# 4x4v3.net
KiCad netlist of a schematic drawn in EAGLE
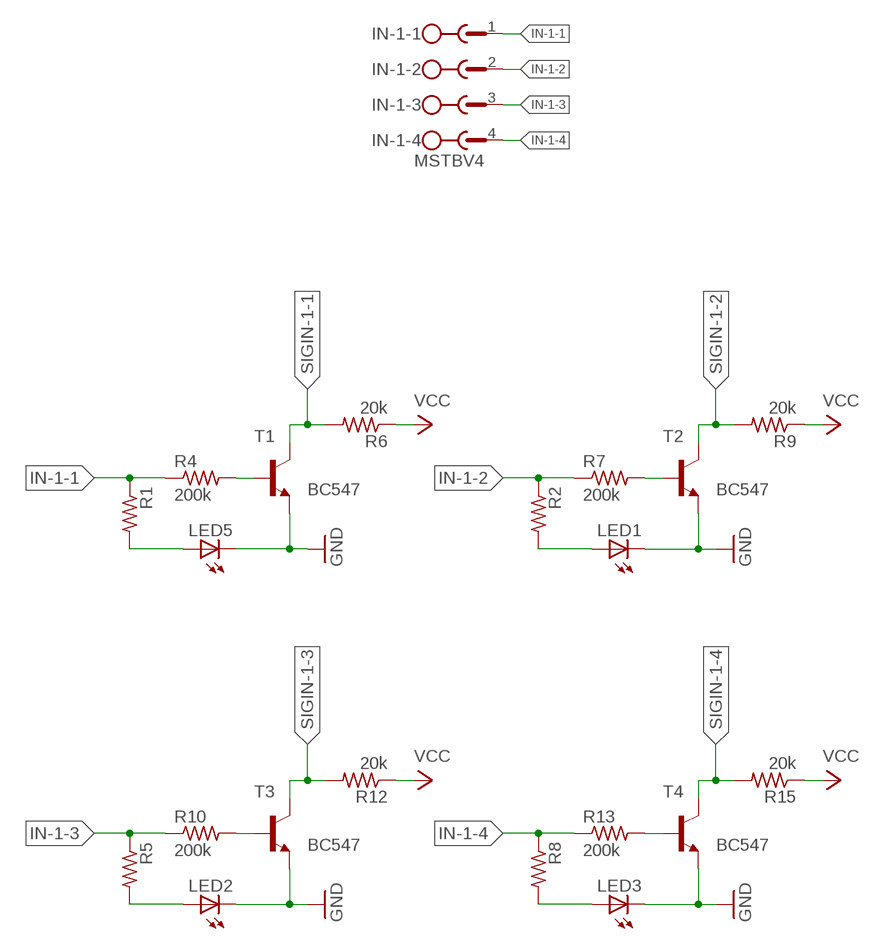
[diagram p0: schematic, sheet 1, part 1 of 2]
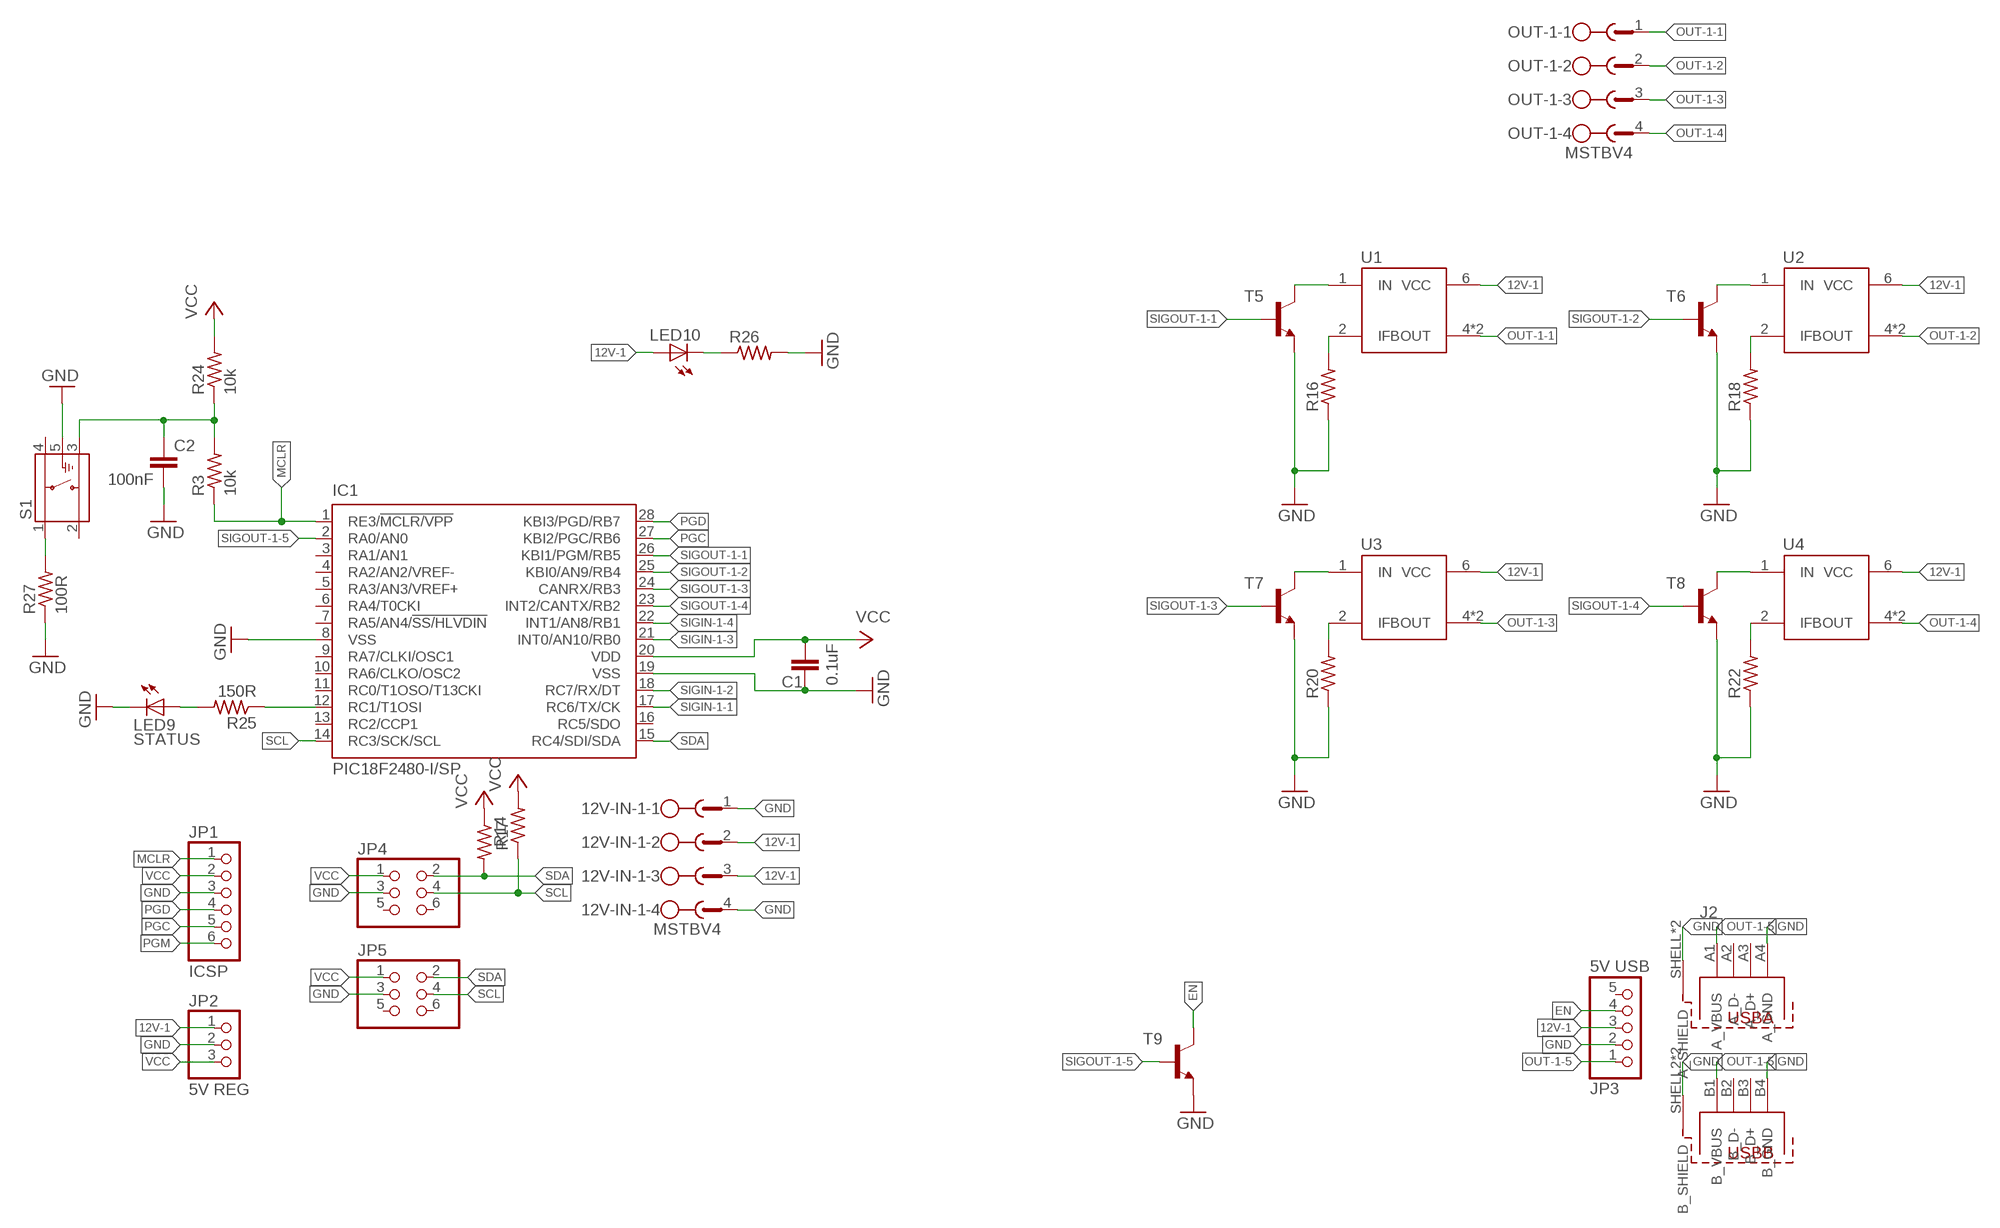
[diagram p1: schematic, sheet 1, part 2 of 2]

(export (version "E")
  (design (tool "Eeschema 10.0.6"))
  (components
    (comp (ref "12V-IN-1")
      (value "MSTBV4")
      (footprint "eagle-import:MSTBV4")
      (fields (field (name "MPN") "MSTBV 2,5/4-GF-5.08"))
      (libsource (lib "eagle-import") (part "MSTBV4"))
    )
    (comp (ref "C1")
      (value "0.1uF")
      (footprint "eagle-import:C025-030X050")
      (libsource (lib "eagle-import") (part "C-EU025-030X050"))
    )
    (comp (ref "C2")
      (value "100nF")
      (footprint "eagle-import:C025-025X050")
      (libsource (lib "eagle-import") (part "C-EU025-025X050"))
    )
    (comp (ref "IC1")
      (value "PIC18F2480-I/SP")
      (footprint "eagle-import:DIL28-3")
      (fields (field (name "MF") "MICROCHIP"))
      (libsource (lib "eagle-import") (part "PIC18F280-I/SP4"))
    )
    (comp (ref "IN-1")
      (value "MSTBV4")
      (footprint "eagle-import:MSTBV4")
      (fields (field (name "MPN") "MSTBV 2,5/4-GF-5.08"))
      (libsource (lib "eagle-import") (part "MSTBV4"))
    )
    (comp (ref "J2")
      (value "614008235023")
      (footprint "eagle-import:614008235023")
      (libsource (lib "eagle-import") (part "614008235023"))
    )
    (comp (ref "JP1")
      (value "ICSP")
      (footprint "eagle-import:1X06")
      (libsource (lib "eagle-import") (part "PINHD-1X6"))
    )
    (comp (ref "JP2")
      (value "5V REG")
      (footprint "eagle-import:1X03")
      (libsource (lib "eagle-import") (part "PINHD-1X3"))
    )
    (comp (ref "JP3")
      (value "5V USB")
      (footprint "eagle-import:1X05")
      (libsource (lib "eagle-import") (part "PINHD-1X5"))
    )
    (comp (ref "JP4")
      (value "PINHD-2X3")
      (footprint "eagle-import:2X03")
      (libsource (lib "eagle-import") (part "PINHD-2X3"))
    )
    (comp (ref "JP5")
      (value "PINHD-2X3")
      (footprint "eagle-import:2X03")
      (libsource (lib "eagle-import") (part "PINHD-2X3"))
    )
    (comp (ref "LED1")
      (value "LEDCHIPLED_0805")
      (footprint "eagle-import:CHIPLED_0805")
      (libsource (lib "eagle-import") (part "LEDCHIPLED_0805"))
    )
    (comp (ref "LED2")
      (value "LEDCHIPLED_0805")
      (footprint "eagle-import:CHIPLED_0805")
      (libsource (lib "eagle-import") (part "LEDCHIPLED_0805"))
    )
    (comp (ref "LED3")
      (value "LEDCHIPLED_0805")
      (footprint "eagle-import:CHIPLED_0805")
      (libsource (lib "eagle-import") (part "LEDCHIPLED_0805"))
    )
    (comp (ref "LED5")
      (value "LEDCHIPLED_0805")
      (footprint "eagle-import:CHIPLED_0805")
      (libsource (lib "eagle-import") (part "LEDCHIPLED_0805"))
    )
    (comp (ref "LED9")
      (value "STATUS")
      (footprint "eagle-import:CHIPLED_0805")
      (libsource (lib "eagle-import") (part "LEDCHIPLED_0805"))
    )
    (comp (ref "LED10")
      (value "LEDCHIPLED_0805")
      (footprint "eagle-import:CHIPLED_0805")
      (libsource (lib "eagle-import") (part "LEDCHIPLED_0805"))
    )
    (comp (ref "OUT-1")
      (value "MSTBV4")
      (footprint "eagle-import:MSTBV4")
      (fields (field (name "MPN") "MSTBV 2,5/4-GF-5.08"))
      (libsource (lib "eagle-import") (part "MSTBV4"))
    )
    (comp (ref "R1")
      (value "R-US_R0805")
      (footprint "eagle-import:R0805")
      (libsource (lib "eagle-import") (part "R-US_R0805"))
    )
    (comp (ref "R2")
      (value "R-US_R0805")
      (footprint "eagle-import:R0805")
      (libsource (lib "eagle-import") (part "R-US_R0805"))
    )
    (comp (ref "R3")
      (value "10k")
      (footprint "eagle-import:R0805")
      (libsource (lib "eagle-import") (part "R-US_R0805"))
    )
    (comp (ref "R4")
      (value "200k")
      (footprint "eagle-import:R0805")
      (libsource (lib "eagle-import") (part "R-US_R0805"))
    )
    (comp (ref "R5")
      (value "R-US_R0805")
      (footprint "eagle-import:R0805")
      (libsource (lib "eagle-import") (part "R-US_R0805"))
    )
    (comp (ref "R6")
      (value "20k")
      (footprint "eagle-import:R0805")
      (libsource (lib "eagle-import") (part "R-US_R0805"))
    )
    (comp (ref "R7")
      (value "200k")
      (footprint "eagle-import:R0805")
      (libsource (lib "eagle-import") (part "R-US_R0805"))
    )
    (comp (ref "R8")
      (value "R-US_R0805")
      (footprint "eagle-import:R0805")
      (libsource (lib "eagle-import") (part "R-US_R0805"))
    )
    (comp (ref "R9")
      (value "20k")
      (footprint "eagle-import:R0805")
      (libsource (lib "eagle-import") (part "R-US_R0805"))
    )
    (comp (ref "R10")
      (value "200k")
      (footprint "eagle-import:R0805")
      (libsource (lib "eagle-import") (part "R-US_R0805"))
    )
    (comp (ref "R12")
      (value "20k")
      (footprint "eagle-import:R0805")
      (libsource (lib "eagle-import") (part "R-US_R0805"))
    )
    (comp (ref "R13")
      (value "200k")
      (footprint "eagle-import:R0805")
      (libsource (lib "eagle-import") (part "R-US_R0805"))
    )
    (comp (ref "R14")
      (value "R-US_R0805")
      (footprint "eagle-import:R0805")
      (libsource (lib "eagle-import") (part "R-US_R0805"))
    )
    (comp (ref "R15")
      (value "20k")
      (footprint "eagle-import:R0805")
      (libsource (lib "eagle-import") (part "R-US_R0805"))
    )
    (comp (ref "R16")
      (value "R-US_R0805")
      (footprint "eagle-import:R0805")
      (libsource (lib "eagle-import") (part "R-US_R0805"))
    )
    (comp (ref "R17")
      (value "R-US_R0805")
      (footprint "eagle-import:R0805")
      (libsource (lib "eagle-import") (part "R-US_R0805"))
    )
    (comp (ref "R18")
      (value "R-US_R0805")
      (footprint "eagle-import:R0805")
      (libsource (lib "eagle-import") (part "R-US_R0805"))
    )
    (comp (ref "R20")
      (value "R-US_R0805")
      (footprint "eagle-import:R0805")
      (libsource (lib "eagle-import") (part "R-US_R0805"))
    )
    (comp (ref "R22")
      (value "R-US_R0805")
      (footprint "eagle-import:R0805")
      (libsource (lib "eagle-import") (part "R-US_R0805"))
    )
    (comp (ref "R24")
      (value "10k")
      (footprint "eagle-import:R0805")
      (libsource (lib "eagle-import") (part "R-US_R0805"))
    )
    (comp (ref "R25")
      (value "150R")
      (footprint "eagle-import:R0805")
      (libsource (lib "eagle-import") (part "R-US_R0805"))
    )
    (comp (ref "R26")
      (value "R-US_R0805")
      (footprint "eagle-import:R0805")
      (libsource (lib "eagle-import") (part "R-US_R0805"))
    )
    (comp (ref "R27")
      (value "100R")
      (footprint "eagle-import:R0805")
      (libsource (lib "eagle-import") (part "R-US_R0805"))
    )
    (comp (ref "S1")
      (value "KMR421GULCLFS")
      (footprint "eagle-import:SW_KMR421GULCLFS")
      (fields (field (name "MF") "C&K Components"))
      (libsource (lib "eagle-import") (part "KMR421GULCLFS"))
    )
    (comp (ref "T1")
      (value "BC547")
      (footprint "eagle-import:SOT23-EBC")
      (libsource (lib "eagle-import") (part "-NPN-SOT23-EBC"))
    )
    (comp (ref "T2")
      (value "BC547")
      (footprint "eagle-import:SOT23-EBC")
      (libsource (lib "eagle-import") (part "-NPN-SOT23-EBC"))
    )
    (comp (ref "T3")
      (value "BC547")
      (footprint "eagle-import:SOT23-EBC")
      (libsource (lib "eagle-import") (part "-NPN-SOT23-EBC"))
    )
    (comp (ref "T4")
      (value "BC547")
      (footprint "eagle-import:SOT23-EBC")
      (libsource (lib "eagle-import") (part "-NPN-SOT23-EBC"))
    )
    (comp (ref "T5")
      (value "-NPN-SOT23-EBC")
      (footprint "eagle-import:SOT23-EBC")
      (libsource (lib "eagle-import") (part "-NPN-SOT23-EBC"))
    )
    (comp (ref "T6")
      (value "-NPN-SOT23-EBC")
      (footprint "eagle-import:SOT23-EBC")
      (libsource (lib "eagle-import") (part "-NPN-SOT23-EBC"))
    )
    (comp (ref "T7")
      (value "-NPN-SOT23-EBC")
      (footprint "eagle-import:SOT23-EBC")
      (libsource (lib "eagle-import") (part "-NPN-SOT23-EBC"))
    )
    (comp (ref "T8")
      (value "-NPN-SOT23-EBC")
      (footprint "eagle-import:SOT23-EBC")
      (libsource (lib "eagle-import") (part "-NPN-SOT23-EBC"))
    )
    (comp (ref "T9")
      (value "-NPN-SOT23-EBC")
      (footprint "eagle-import:SOT23-EBC")
      (libsource (lib "eagle-import") (part "-NPN-SOT23-EBC"))
    )
    (comp (ref "U1")
      (value "IR3315")
      (footprint "eagle-import:TO263-5")
      (libsource (lib "eagle-import") (part "IR3315"))
    )
    (comp (ref "U2")
      (value "IR3315")
      (footprint "eagle-import:TO263-5")
      (libsource (lib "eagle-import") (part "IR3315"))
    )
    (comp (ref "U3")
      (value "IR3315")
      (footprint "eagle-import:TO263-5")
      (libsource (lib "eagle-import") (part "IR3315"))
    )
    (comp (ref "U4")
      (value "IR3315")
      (footprint "eagle-import:TO263-5")
      (libsource (lib "eagle-import") (part "IR3315"))
    )
  )
  (nets
    (net (code "1") (name "12V-1") (class "Default")
      (node (ref "12V-IN-1") (pin "2") (pinfunction "1_2") (pintype "passive"))
      (node (ref "12V-IN-1") (pin "3") (pinfunction "1_3") (pintype "passive"))
      (node (ref "JP2") (pin "1") (pinfunction "1_1") (pintype "passive"))
      (node (ref "JP3") (pin "3") (pinfunction "3_3") (pintype "passive"))
      (node (ref "LED10") (pin "A") (pinfunction "A_A") (pintype "passive"))
      (node (ref "U1") (pin "6") (pinfunction "VCC_6") (pintype "bidirectional"))
      (node (ref "U2") (pin "6") (pinfunction "VCC_6") (pintype "bidirectional"))
      (node (ref "U3") (pin "6") (pinfunction "VCC_6") (pintype "bidirectional"))
      (node (ref "U4") (pin "6") (pinfunction "VCC_6") (pintype "bidirectional"))
    )
    (net (code "2") (name "EN") (class "Default")
      (node (ref "JP3") (pin "4") (pinfunction "4_4") (pintype "passive"))
      (node (ref "T9") (pin "C") (pinfunction "C_C") (pintype "passive"))
    )
    (net (code "3") (name "GND") (class "Default")
      (node (ref "12V-IN-1") (pin "1") (pinfunction "1_1") (pintype "passive"))
      (node (ref "12V-IN-1") (pin "4") (pinfunction "1_4") (pintype "passive"))
      (node (ref "C1") (pin "2") (pinfunction "2_2") (pintype "passive"))
      (node (ref "C2") (pin "2") (pinfunction "2_2") (pintype "passive"))
      (node (ref "IC1") (pin "19") (pinfunction "VSS_19") (pintype "power_in"))
      (node (ref "IC1") (pin "8") (pinfunction "VSS_8") (pintype "power_in"))
      (node (ref "J2") (pin "A4") (pinfunction "A_GND_A4") (pintype "bidirectional"))
      (node (ref "J2") (pin "B4") (pinfunction "B_GND_B4") (pintype "bidirectional"))
      (node (ref "J2") (pin "SHELL") (pinfunction "A_SHIELD_SHELL") (pintype "bidirectional"))
      (node (ref "J2") (pin "SHELL1") (pinfunction "A_SHIELD_SHELL1") (pintype "bidirectional"))
      (node (ref "J2") (pin "SHELL2") (pinfunction "B_SHIELD_SHELL2") (pintype "bidirectional"))
      (node (ref "J2") (pin "SHELL3") (pinfunction "B_SHIELD_SHELL3") (pintype "bidirectional"))
      (node (ref "JP1") (pin "3") (pinfunction "3_3") (pintype "passive"))
      (node (ref "JP2") (pin "2") (pinfunction "2_2") (pintype "passive"))
      (node (ref "JP3") (pin "2") (pinfunction "2_2") (pintype "passive"))
      (node (ref "JP4") (pin "3") (pinfunction "3_3") (pintype "passive"))
      (node (ref "JP5") (pin "3") (pinfunction "3_3") (pintype "passive"))
      (node (ref "LED1") (pin "C") (pinfunction "C_C") (pintype "passive"))
      (node (ref "LED2") (pin "C") (pinfunction "C_C") (pintype "passive"))
      (node (ref "LED3") (pin "C") (pinfunction "C_C") (pintype "passive"))
      (node (ref "LED5") (pin "C") (pinfunction "C_C") (pintype "passive"))
      (node (ref "LED9") (pin "C") (pinfunction "C_C") (pintype "passive"))
      (node (ref "R16") (pin "1") (pinfunction "1_1") (pintype "passive"))
      (node (ref "R18") (pin "1") (pinfunction "1_1") (pintype "passive"))
      (node (ref "R20") (pin "1") (pinfunction "1_1") (pintype "passive"))
      (node (ref "R22") (pin "1") (pinfunction "1_1") (pintype "passive"))
      (node (ref "R26") (pin "2") (pinfunction "2_2") (pintype "passive"))
      (node (ref "R27") (pin "1") (pinfunction "1_1") (pintype "passive"))
      (node (ref "S1") (pin "5") (pinfunction "G_5") (pintype "power_in"))
      (node (ref "T1") (pin "E") (pinfunction "E_E") (pintype "passive"))
      (node (ref "T2") (pin "E") (pinfunction "E_E") (pintype "passive"))
      (node (ref "T3") (pin "E") (pinfunction "E_E") (pintype "passive"))
      (node (ref "T4") (pin "E") (pinfunction "E_E") (pintype "passive"))
      (node (ref "T5") (pin "E") (pinfunction "E_E") (pintype "passive"))
      (node (ref "T6") (pin "E") (pinfunction "E_E") (pintype "passive"))
      (node (ref "T7") (pin "E") (pinfunction "E_E") (pintype "passive"))
      (node (ref "T8") (pin "E") (pinfunction "E_E") (pintype "passive"))
      (node (ref "T9") (pin "E") (pinfunction "E_E") (pintype "passive"))
    )
    (net (code "4") (name "IN-1-1") (class "Default")
      (node (ref "IN-1") (pin "1") (pinfunction "1_1") (pintype "passive"))
      (node (ref "R1") (pin "1") (pinfunction "1_1") (pintype "passive"))
      (node (ref "R4") (pin "1") (pinfunction "1_1") (pintype "passive"))
    )
    (net (code "5") (name "IN-1-2") (class "Default")
      (node (ref "IN-1") (pin "2") (pinfunction "1_2") (pintype "passive"))
      (node (ref "R2") (pin "1") (pinfunction "1_1") (pintype "passive"))
      (node (ref "R7") (pin "1") (pinfunction "1_1") (pintype "passive"))
    )
    (net (code "6") (name "IN-1-3") (class "Default")
      (node (ref "IN-1") (pin "3") (pinfunction "1_3") (pintype "passive"))
      (node (ref "R10") (pin "1") (pinfunction "1_1") (pintype "passive"))
      (node (ref "R5") (pin "1") (pinfunction "1_1") (pintype "passive"))
    )
    (net (code "7") (name "IN-1-4") (class "Default")
      (node (ref "IN-1") (pin "4") (pinfunction "1_4") (pintype "passive"))
      (node (ref "R13") (pin "1") (pinfunction "1_1") (pintype "passive"))
      (node (ref "R8") (pin "1") (pinfunction "1_1") (pintype "passive"))
    )
    (net (code "8") (name "MCLR") (class "Default")
      (node (ref "IC1") (pin "1") (pinfunction "RE3/~{MCLR/VPP}_1") (pintype "input"))
      (node (ref "JP1") (pin "1") (pinfunction "1_1") (pintype "passive"))
      (node (ref "R3") (pin "1") (pinfunction "1_1") (pintype "passive"))
    )
    (net (code "9") (name "Net-(C2-Pad1)") (class "Default")
      (node (ref "C2") (pin "1") (pinfunction "1_1") (pintype "passive"))
      (node (ref "R24") (pin "1") (pinfunction "1_1") (pintype "passive"))
      (node (ref "R3") (pin "2") (pinfunction "2_2") (pintype "passive"))
      (node (ref "S1") (pin "3") (pinfunction "3_3") (pintype "passive"))
    )
    (net (code "10") (name "Net-(IC1-RC1{slash}T1OSI)") (class "Default")
      (node (ref "IC1") (pin "12") (pinfunction "RC1/T1OSI_12") (pintype "bidirectional"))
      (node (ref "R25") (pin "1") (pinfunction "1_1") (pintype "passive"))
    )
    (net (code "11") (name "Net-(LED1-PadA)") (class "Default")
      (node (ref "LED1") (pin "A") (pinfunction "A_A") (pintype "passive"))
      (node (ref "R2") (pin "2") (pinfunction "2_2") (pintype "passive"))
    )
    (net (code "12") (name "Net-(LED2-PadA)") (class "Default")
      (node (ref "LED2") (pin "A") (pinfunction "A_A") (pintype "passive"))
      (node (ref "R5") (pin "2") (pinfunction "2_2") (pintype "passive"))
    )
    (net (code "13") (name "Net-(LED3-PadA)") (class "Default")
      (node (ref "LED3") (pin "A") (pinfunction "A_A") (pintype "passive"))
      (node (ref "R8") (pin "2") (pinfunction "2_2") (pintype "passive"))
    )
    (net (code "14") (name "Net-(LED5-PadA)") (class "Default")
      (node (ref "LED5") (pin "A") (pinfunction "A_A") (pintype "passive"))
      (node (ref "R1") (pin "2") (pinfunction "2_2") (pintype "passive"))
    )
    (net (code "15") (name "Net-(LED9-PadA)") (class "Default")
      (node (ref "LED9") (pin "A") (pinfunction "A_A") (pintype "passive"))
      (node (ref "R25") (pin "2") (pinfunction "2_2") (pintype "passive"))
    )
    (net (code "16") (name "Net-(LED10-PadC)") (class "Default")
      (node (ref "LED10") (pin "C") (pinfunction "C_C") (pintype "passive"))
      (node (ref "R26") (pin "1") (pinfunction "1_1") (pintype "passive"))
    )
    (net (code "17") (name "Net-(R4-Pad2)") (class "Default")
      (node (ref "R4") (pin "2") (pinfunction "2_2") (pintype "passive"))
      (node (ref "T1") (pin "B") (pinfunction "B_B") (pintype "passive"))
    )
    (net (code "18") (name "Net-(R7-Pad2)") (class "Default")
      (node (ref "R7") (pin "2") (pinfunction "2_2") (pintype "passive"))
      (node (ref "T2") (pin "B") (pinfunction "B_B") (pintype "passive"))
    )
    (net (code "19") (name "Net-(R10-Pad2)") (class "Default")
      (node (ref "R10") (pin "2") (pinfunction "2_2") (pintype "passive"))
      (node (ref "T3") (pin "B") (pinfunction "B_B") (pintype "passive"))
    )
    (net (code "20") (name "Net-(R13-Pad2)") (class "Default")
      (node (ref "R13") (pin "2") (pinfunction "2_2") (pintype "passive"))
      (node (ref "T4") (pin "B") (pinfunction "B_B") (pintype "passive"))
    )
    (net (code "21") (name "Net-(R27-Pad2)") (class "Default")
      (node (ref "R27") (pin "2") (pinfunction "2_2") (pintype "passive"))
      (node (ref "S1") (pin "1") (pinfunction "1_1") (pintype "passive"))
    )
    (net (code "22") (name "Net-(U1-IFB)") (class "Default")
      (node (ref "R16") (pin "2") (pinfunction "2_2") (pintype "passive"))
      (node (ref "U1") (pin "2") (pinfunction "IFB_2") (pintype "bidirectional"))
    )
    (net (code "23") (name "Net-(U1-IN)") (class "Default")
      (node (ref "T5") (pin "C") (pinfunction "C_C") (pintype "passive"))
      (node (ref "U1") (pin "1") (pinfunction "IN_1") (pintype "bidirectional"))
    )
    (net (code "24") (name "Net-(U2-IFB)") (class "Default")
      (node (ref "R18") (pin "2") (pinfunction "2_2") (pintype "passive"))
      (node (ref "U2") (pin "2") (pinfunction "IFB_2") (pintype "bidirectional"))
    )
    (net (code "25") (name "Net-(U2-IN)") (class "Default")
      (node (ref "T6") (pin "C") (pinfunction "C_C") (pintype "passive"))
      (node (ref "U2") (pin "1") (pinfunction "IN_1") (pintype "bidirectional"))
    )
    (net (code "26") (name "Net-(U3-IFB)") (class "Default")
      (node (ref "R20") (pin "2") (pinfunction "2_2") (pintype "passive"))
      (node (ref "U3") (pin "2") (pinfunction "IFB_2") (pintype "bidirectional"))
    )
    (net (code "27") (name "Net-(U3-IN)") (class "Default")
      (node (ref "T7") (pin "C") (pinfunction "C_C") (pintype "passive"))
      (node (ref "U3") (pin "1") (pinfunction "IN_1") (pintype "bidirectional"))
    )
    (net (code "28") (name "Net-(U4-IFB)") (class "Default")
      (node (ref "R22") (pin "2") (pinfunction "2_2") (pintype "passive"))
      (node (ref "U4") (pin "2") (pinfunction "IFB_2") (pintype "bidirectional"))
    )
    (net (code "29") (name "Net-(U4-IN)") (class "Default")
      (node (ref "T8") (pin "C") (pinfunction "C_C") (pintype "passive"))
      (node (ref "U4") (pin "1") (pinfunction "IN_1") (pintype "bidirectional"))
    )
    (net (code "30") (name "OUT-1-1") (class "Default")
      (node (ref "OUT-1") (pin "1") (pinfunction "1_1") (pintype "passive"))
      (node (ref "U1") (pin "4") (pinfunction "OUT_4") (pintype "bidirectional"))
      (node (ref "U1") (pin "5") (pinfunction "OUT_5") (pintype "bidirectional"))
    )
    (net (code "31") (name "OUT-1-2") (class "Default")
      (node (ref "OUT-1") (pin "2") (pinfunction "1_2") (pintype "passive"))
      (node (ref "U2") (pin "4") (pinfunction "OUT_4") (pintype "bidirectional"))
      (node (ref "U2") (pin "5") (pinfunction "OUT_5") (pintype "bidirectional"))
    )
    (net (code "32") (name "OUT-1-3") (class "Default")
      (node (ref "OUT-1") (pin "3") (pinfunction "1_3") (pintype "passive"))
      (node (ref "U3") (pin "4") (pinfunction "OUT_4") (pintype "bidirectional"))
      (node (ref "U3") (pin "5") (pinfunction "OUT_5") (pintype "bidirectional"))
    )
    (net (code "33") (name "OUT-1-4") (class "Default")
      (node (ref "OUT-1") (pin "4") (pinfunction "1_4") (pintype "passive"))
      (node (ref "U4") (pin "4") (pinfunction "OUT_4") (pintype "bidirectional"))
      (node (ref "U4") (pin "5") (pinfunction "OUT_5") (pintype "bidirectional"))
    )
    (net (code "34") (name "OUT-1-5") (class "Default")
      (node (ref "J2") (pin "A1") (pinfunction "A_VBUS_A1") (pintype "bidirectional"))
      (node (ref "J2") (pin "B1") (pinfunction "B_VBUS_B1") (pintype "bidirectional"))
      (node (ref "JP3") (pin "1") (pinfunction "1_1") (pintype "passive"))
    )
    (net (code "35") (name "PGC") (class "Default")
      (node (ref "IC1") (pin "27") (pinfunction "KBI2/PGC/RB6_27") (pintype "bidirectional"))
      (node (ref "JP1") (pin "5") (pinfunction "5_5") (pintype "passive"))
    )
    (net (code "36") (name "PGD") (class "Default")
      (node (ref "IC1") (pin "28") (pinfunction "KBI3/PGD/RB7_28") (pintype "bidirectional"))
      (node (ref "JP1") (pin "4") (pinfunction "4_4") (pintype "passive"))
    )
    (net (code "37") (name "PGM") (class "Default")
      (node (ref "JP1") (pin "6") (pinfunction "6_6") (pintype "passive"))
    )
    (net (code "38") (name "SCL") (class "Default")
      (node (ref "IC1") (pin "14") (pinfunction "RC3/SCK/SCL_14") (pintype "bidirectional"))
      (node (ref "JP4") (pin "4") (pinfunction "4_4") (pintype "passive"))
      (node (ref "JP5") (pin "4") (pinfunction "4_4") (pintype "passive"))
      (node (ref "R17") (pin "1") (pinfunction "1_1") (pintype "passive"))
    )
    (net (code "39") (name "SDA") (class "Default")
      (node (ref "IC1") (pin "15") (pinfunction "RC4/SDI/SDA_15") (pintype "bidirectional"))
      (node (ref "JP4") (pin "2") (pinfunction "2_2") (pintype "passive"))
      (node (ref "JP5") (pin "2") (pinfunction "2_2") (pintype "passive"))
      (node (ref "R14") (pin "2") (pinfunction "2_2") (pintype "passive"))
    )
    (net (code "40") (name "SIGIN-1-1") (class "Default")
      (node (ref "IC1") (pin "17") (pinfunction "RC6/TX/CK_17") (pintype "bidirectional"))
      (node (ref "R6") (pin "2") (pinfunction "2_2") (pintype "passive"))
      (node (ref "T1") (pin "C") (pinfunction "C_C") (pintype "passive"))
    )
    (net (code "41") (name "SIGIN-1-2") (class "Default")
      (node (ref "IC1") (pin "18") (pinfunction "RC7/RX/DT_18") (pintype "bidirectional"))
      (node (ref "R9") (pin "2") (pinfunction "2_2") (pintype "passive"))
      (node (ref "T2") (pin "C") (pinfunction "C_C") (pintype "passive"))
    )
    (net (code "42") (name "SIGIN-1-3") (class "Default")
      (node (ref "IC1") (pin "21") (pinfunction "INT0/AN10/RB0_21") (pintype "bidirectional"))
      (node (ref "R12") (pin "2") (pinfunction "2_2") (pintype "passive"))
      (node (ref "T3") (pin "C") (pinfunction "C_C") (pintype "passive"))
    )
    (net (code "43") (name "SIGIN-1-4") (class "Default")
      (node (ref "IC1") (pin "22") (pinfunction "INT1/AN8/RB1_22") (pintype "bidirectional"))
      (node (ref "R15") (pin "2") (pinfunction "2_2") (pintype "passive"))
      (node (ref "T4") (pin "C") (pinfunction "C_C") (pintype "passive"))
    )
    (net (code "44") (name "SIGOUT-1-1") (class "Default")
      (node (ref "IC1") (pin "26") (pinfunction "KBI1/PGM/RB5_26") (pintype "bidirectional"))
      (node (ref "T5") (pin "B") (pinfunction "B_B") (pintype "passive"))
    )
    (net (code "45") (name "SIGOUT-1-2") (class "Default")
      (node (ref "IC1") (pin "25") (pinfunction "KBI0/AN9/RB4_25") (pintype "bidirectional"))
      (node (ref "T6") (pin "B") (pinfunction "B_B") (pintype "passive"))
    )
    (net (code "46") (name "SIGOUT-1-3") (class "Default")
      (node (ref "IC1") (pin "24") (pinfunction "CANRX/RB3_24") (pintype "bidirectional"))
      (node (ref "T7") (pin "B") (pinfunction "B_B") (pintype "passive"))
    )
    (net (code "47") (name "SIGOUT-1-4") (class "Default")
      (node (ref "IC1") (pin "23") (pinfunction "INT2/CANTX/RB2_23") (pintype "bidirectional"))
      (node (ref "T8") (pin "B") (pinfunction "B_B") (pintype "passive"))
    )
    (net (code "48") (name "SIGOUT-1-5") (class "Default")
      (node (ref "IC1") (pin "2") (pinfunction "RA0/AN0_2") (pintype "bidirectional"))
      (node (ref "T9") (pin "B") (pinfunction "B_B") (pintype "passive"))
    )
    (net (code "49") (name "VCC") (class "Default")
      (node (ref "C1") (pin "1") (pinfunction "1_1") (pintype "passive"))
      (node (ref "IC1") (pin "20") (pinfunction "VDD_20") (pintype "power_in"))
      (node (ref "JP1") (pin "2") (pinfunction "2_2") (pintype "passive"))
      (node (ref "JP2") (pin "3") (pinfunction "3_3") (pintype "passive"))
      (node (ref "JP4") (pin "1") (pinfunction "1_1") (pintype "passive"))
      (node (ref "JP5") (pin "1") (pinfunction "1_1") (pintype "passive"))
      (node (ref "R12") (pin "1") (pinfunction "1_1") (pintype "passive"))
      (node (ref "R14") (pin "1") (pinfunction "1_1") (pintype "passive"))
      (node (ref "R15") (pin "1") (pinfunction "1_1") (pintype "passive"))
      (node (ref "R17") (pin "2") (pinfunction "2_2") (pintype "passive"))
      (node (ref "R24") (pin "2") (pinfunction "2_2") (pintype "passive"))
      (node (ref "R6") (pin "1") (pinfunction "1_1") (pintype "passive"))
      (node (ref "R9") (pin "1") (pinfunction "1_1") (pintype "passive"))
    )
    (net (code "50") (name "unconnected-(IC1-RA1{slash}AN1-Pad3)") (class "Default")
      (node (ref "IC1") (pin "3") (pinfunction "RA1/AN1_3") (pintype "bidirectional"))
    )
    (net (code "51") (name "unconnected-(IC1-RA2{slash}AN2{slash}VREF--Pad4)") (class "Default")
      (node (ref "IC1") (pin "4") (pinfunction "RA2/AN2/VREF-_4") (pintype "bidirectional"))
    )
    (net (code "52") (name "unconnected-(IC1-RA3{slash}AN3{slash}VREF+-Pad5)") (class "Default")
      (node (ref "IC1") (pin "5") (pinfunction "RA3/AN3/VREF+_5") (pintype "bidirectional"))
    )
    (net (code "53") (name "unconnected-(IC1-RA4{slash}T0CKI-Pad6)") (class "Default")
      (node (ref "IC1") (pin "6") (pinfunction "RA4/T0CKI_6") (pintype "bidirectional"))
    )
    (net (code "54") (name "unconnected-(IC1-RA5{slash}AN4{slash}~{SS{slash}HLVDIN}-Pad7)") (class "Default")
      (node (ref "IC1") (pin "7") (pinfunction "RA5/AN4/~{SS/HLVDIN}_7") (pintype "bidirectional"))
    )
    (net (code "55") (name "unconnected-(IC1-RA6{slash}CLKO{slash}OSC2-Pad10)") (class "Default")
      (node (ref "IC1") (pin "10") (pinfunction "RA6/CLKO/OSC2_10") (pintype "output"))
    )
    (net (code "56") (name "unconnected-(IC1-RA7{slash}CLKI{slash}OSC1-Pad9)") (class "Default")
      (node (ref "IC1") (pin "9") (pinfunction "RA7/CLKI/OSC1_9") (pintype "input"))
    )
    (net (code "57") (name "unconnected-(IC1-RC0{slash}T1OSO{slash}T13CKI-Pad11)") (class "Default")
      (node (ref "IC1") (pin "11") (pinfunction "RC0/T1OSO/T13CKI_11") (pintype "bidirectional"))
    )
    (net (code "58") (name "unconnected-(IC1-RC2{slash}CCP1-Pad13)") (class "Default")
      (node (ref "IC1") (pin "13") (pinfunction "RC2/CCP1_13") (pintype "bidirectional"))
    )
    (net (code "59") (name "unconnected-(IC1-RC5{slash}SDO-Pad16)") (class "Default")
      (node (ref "IC1") (pin "16") (pinfunction "RC5/SDO_16") (pintype "bidirectional"))
    )
    (net (code "60") (name "unconnected-(J2-A_D+-PadA3)") (class "Default")
      (node (ref "J2") (pin "A3") (pinfunction "A_D+_A3") (pintype "bidirectional"))
    )
    (net (code "61") (name "unconnected-(J2-A_D--PadA2)") (class "Default")
      (node (ref "J2") (pin "A2") (pinfunction "A_D-_A2") (pintype "bidirectional"))
    )
    (net (code "62") (name "unconnected-(J2-B_D+-PadB3)") (class "Default")
      (node (ref "J2") (pin "B3") (pinfunction "B_D+_B3") (pintype "bidirectional"))
    )
    (net (code "63") (name "unconnected-(J2-B_D--PadB2)") (class "Default")
      (node (ref "J2") (pin "B2") (pinfunction "B_D-_B2") (pintype "bidirectional"))
    )
    (net (code "64") (name "unconnected-(JP3-Pad5)") (class "Default")
      (node (ref "JP3") (pin "5") (pinfunction "5_5") (pintype "passive"))
    )
    (net (code "65") (name "unconnected-(JP4-Pad5)") (class "Default")
      (node (ref "JP4") (pin "5") (pinfunction "5_5") (pintype "passive"))
    )
    (net (code "66") (name "unconnected-(JP4-Pad6)") (class "Default")
      (node (ref "JP4") (pin "6") (pinfunction "6_6") (pintype "passive"))
    )
    (net (code "67") (name "unconnected-(JP5-Pad5)") (class "Default")
      (node (ref "JP5") (pin "5") (pinfunction "5_5") (pintype "passive"))
    )
    (net (code "68") (name "unconnected-(JP5-Pad6)") (class "Default")
      (node (ref "JP5") (pin "6") (pinfunction "6_6") (pintype "passive"))
    )
    (net (code "69") (name "unconnected-(S1-Pad2)") (class "Default")
      (node (ref "S1") (pin "2") (pinfunction "2_2") (pintype "passive"))
    )
    (net (code "70") (name "unconnected-(S1-Pad4)") (class "Default")
      (node (ref "S1") (pin "4") (pinfunction "4_4") (pintype "passive"))
    )
  )
)
